# SparkFun_Adapter-SSOP20-v10.net
KiCad netlist of a schematic drawn in EAGLE
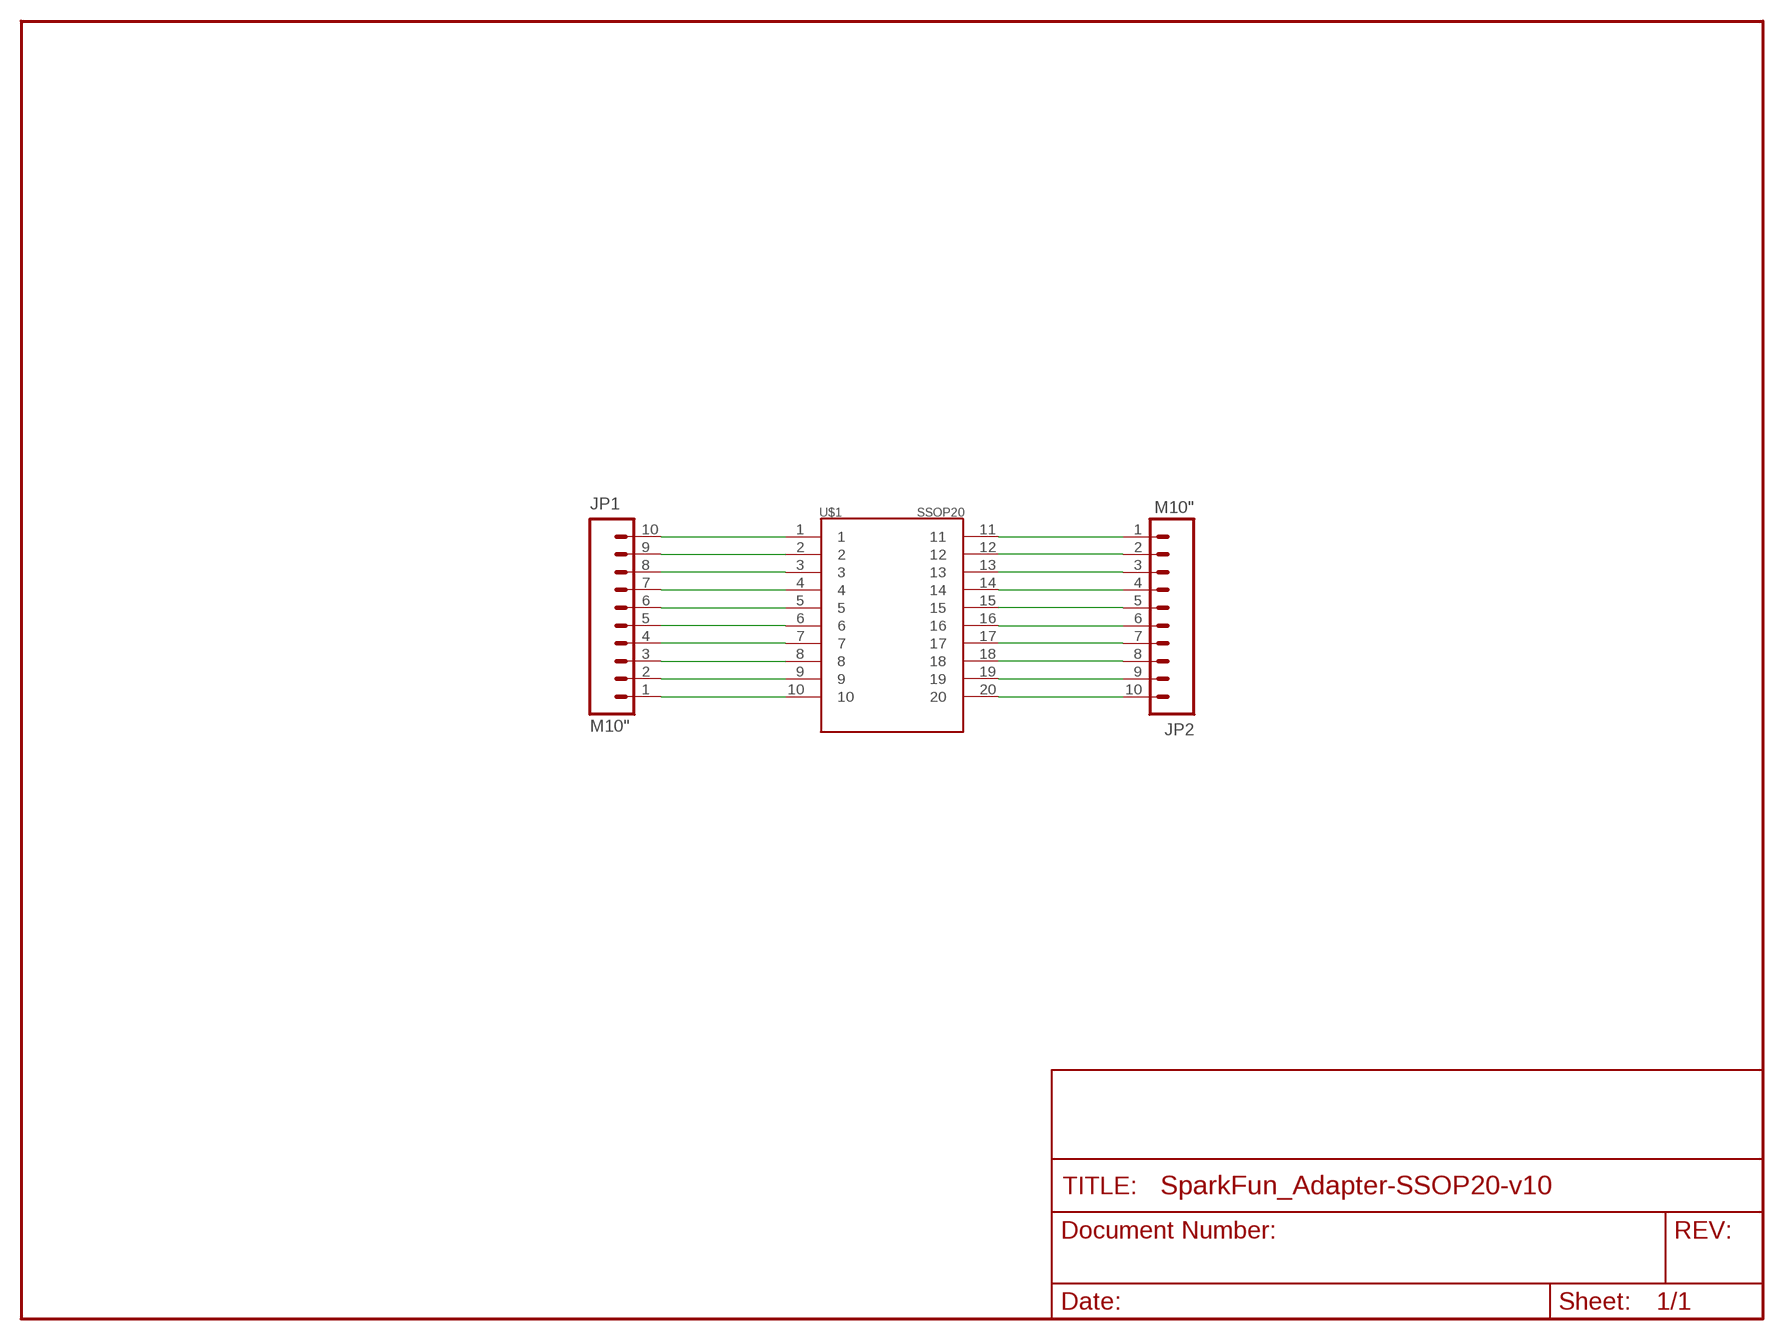
[diagram p0: schematic, sheet 1]

(export (version "E")
  (design (tool "Eeschema 10.0.6"))
  (components
    (comp (ref "JP1")
      (value "M10\"")
      (footprint "eagle-import:1X10")
      (libsource (lib "eagle-import") (part "M10{dblquote}"))
    )
    (comp (ref "JP2")
      (value "M10\"")
      (footprint "eagle-import:1X10")
      (libsource (lib "eagle-import") (part "M10{dblquote}"))
    )
    (comp (ref "U$1")
      (value "SSOP20")
      (footprint "eagle-import:SSOP20-LONG")
      (libsource (lib "eagle-import") (part "SSOP20"))
    )
  )
  (nets
    (net (code "1") (name "Net-(JP1-Pad1)") (class "Default")
      (node (ref "JP1") (pin "1") (pinfunction "1_1") (pintype "passive"))
      (node (ref "U$1") (pin "10") (pinfunction "10_10") (pintype "bidirectional"))
    )
    (net (code "2") (name "Net-(JP1-Pad2)") (class "Default")
      (node (ref "JP1") (pin "2") (pinfunction "2_2") (pintype "passive"))
      (node (ref "U$1") (pin "9") (pinfunction "9_9") (pintype "bidirectional"))
    )
    (net (code "3") (name "Net-(JP1-Pad3)") (class "Default")
      (node (ref "JP1") (pin "3") (pinfunction "3_3") (pintype "passive"))
      (node (ref "U$1") (pin "8") (pinfunction "8_8") (pintype "bidirectional"))
    )
    (net (code "4") (name "Net-(JP1-Pad4)") (class "Default")
      (node (ref "JP1") (pin "4") (pinfunction "4_4") (pintype "passive"))
      (node (ref "U$1") (pin "7") (pinfunction "7_7") (pintype "bidirectional"))
    )
    (net (code "5") (name "Net-(JP1-Pad5)") (class "Default")
      (node (ref "JP1") (pin "5") (pinfunction "5_5") (pintype "passive"))
      (node (ref "U$1") (pin "6") (pinfunction "6_6") (pintype "bidirectional"))
    )
    (net (code "6") (name "Net-(JP1-Pad6)") (class "Default")
      (node (ref "JP1") (pin "6") (pinfunction "6_6") (pintype "passive"))
      (node (ref "U$1") (pin "5") (pinfunction "5_5") (pintype "bidirectional"))
    )
    (net (code "7") (name "Net-(JP1-Pad7)") (class "Default")
      (node (ref "JP1") (pin "7") (pinfunction "7_7") (pintype "passive"))
      (node (ref "U$1") (pin "4") (pinfunction "4_4") (pintype "bidirectional"))
    )
    (net (code "8") (name "Net-(JP1-Pad8)") (class "Default")
      (node (ref "JP1") (pin "8") (pinfunction "8_8") (pintype "passive"))
      (node (ref "U$1") (pin "3") (pinfunction "3_3") (pintype "bidirectional"))
    )
    (net (code "9") (name "Net-(JP1-Pad9)") (class "Default")
      (node (ref "JP1") (pin "9") (pinfunction "9_9") (pintype "passive"))
      (node (ref "U$1") (pin "2") (pinfunction "2_2") (pintype "bidirectional"))
    )
    (net (code "10") (name "Net-(JP1-Pad10)") (class "Default")
      (node (ref "JP1") (pin "10") (pinfunction "10_10") (pintype "passive"))
      (node (ref "U$1") (pin "1") (pinfunction "1_1") (pintype "bidirectional"))
    )
    (net (code "11") (name "Net-(JP2-Pad1)") (class "Default")
      (node (ref "JP2") (pin "1") (pinfunction "1_1") (pintype "passive"))
      (node (ref "U$1") (pin "11") (pinfunction "11_11") (pintype "bidirectional"))
    )
    (net (code "12") (name "Net-(JP2-Pad2)") (class "Default")
      (node (ref "JP2") (pin "2") (pinfunction "2_2") (pintype "passive"))
      (node (ref "U$1") (pin "12") (pinfunction "12_12") (pintype "bidirectional"))
    )
    (net (code "13") (name "Net-(JP2-Pad3)") (class "Default")
      (node (ref "JP2") (pin "3") (pinfunction "3_3") (pintype "passive"))
      (node (ref "U$1") (pin "13") (pinfunction "13_13") (pintype "bidirectional"))
    )
    (net (code "14") (name "Net-(JP2-Pad4)") (class "Default")
      (node (ref "JP2") (pin "4") (pinfunction "4_4") (pintype "passive"))
      (node (ref "U$1") (pin "14") (pinfunction "14_14") (pintype "bidirectional"))
    )
    (net (code "15") (name "Net-(JP2-Pad5)") (class "Default")
      (node (ref "JP2") (pin "5") (pinfunction "5_5") (pintype "passive"))
      (node (ref "U$1") (pin "15") (pinfunction "15_15") (pintype "bidirectional"))
    )
    (net (code "16") (name "Net-(JP2-Pad6)") (class "Default")
      (node (ref "JP2") (pin "6") (pinfunction "6_6") (pintype "passive"))
      (node (ref "U$1") (pin "16") (pinfunction "16_16") (pintype "bidirectional"))
    )
    (net (code "17") (name "Net-(JP2-Pad7)") (class "Default")
      (node (ref "JP2") (pin "7") (pinfunction "7_7") (pintype "passive"))
      (node (ref "U$1") (pin "17") (pinfunction "17_17") (pintype "bidirectional"))
    )
    (net (code "18") (name "Net-(JP2-Pad8)") (class "Default")
      (node (ref "JP2") (pin "8") (pinfunction "8_8") (pintype "passive"))
      (node (ref "U$1") (pin "18") (pinfunction "18_18") (pintype "bidirectional"))
    )
    (net (code "19") (name "Net-(JP2-Pad9)") (class "Default")
      (node (ref "JP2") (pin "9") (pinfunction "9_9") (pintype "passive"))
      (node (ref "U$1") (pin "19") (pinfunction "19_19") (pintype "bidirectional"))
    )
    (net (code "20") (name "Net-(JP2-Pad10)") (class "Default")
      (node (ref "JP2") (pin "10") (pinfunction "10_10") (pintype "passive"))
      (node (ref "U$1") (pin "20") (pinfunction "20_20") (pintype "bidirectional"))
    )
  )
)
